# Doodlebot_v2_2025-06-04.net
KiCad netlist of a schematic drawn in EasyEDA Pro
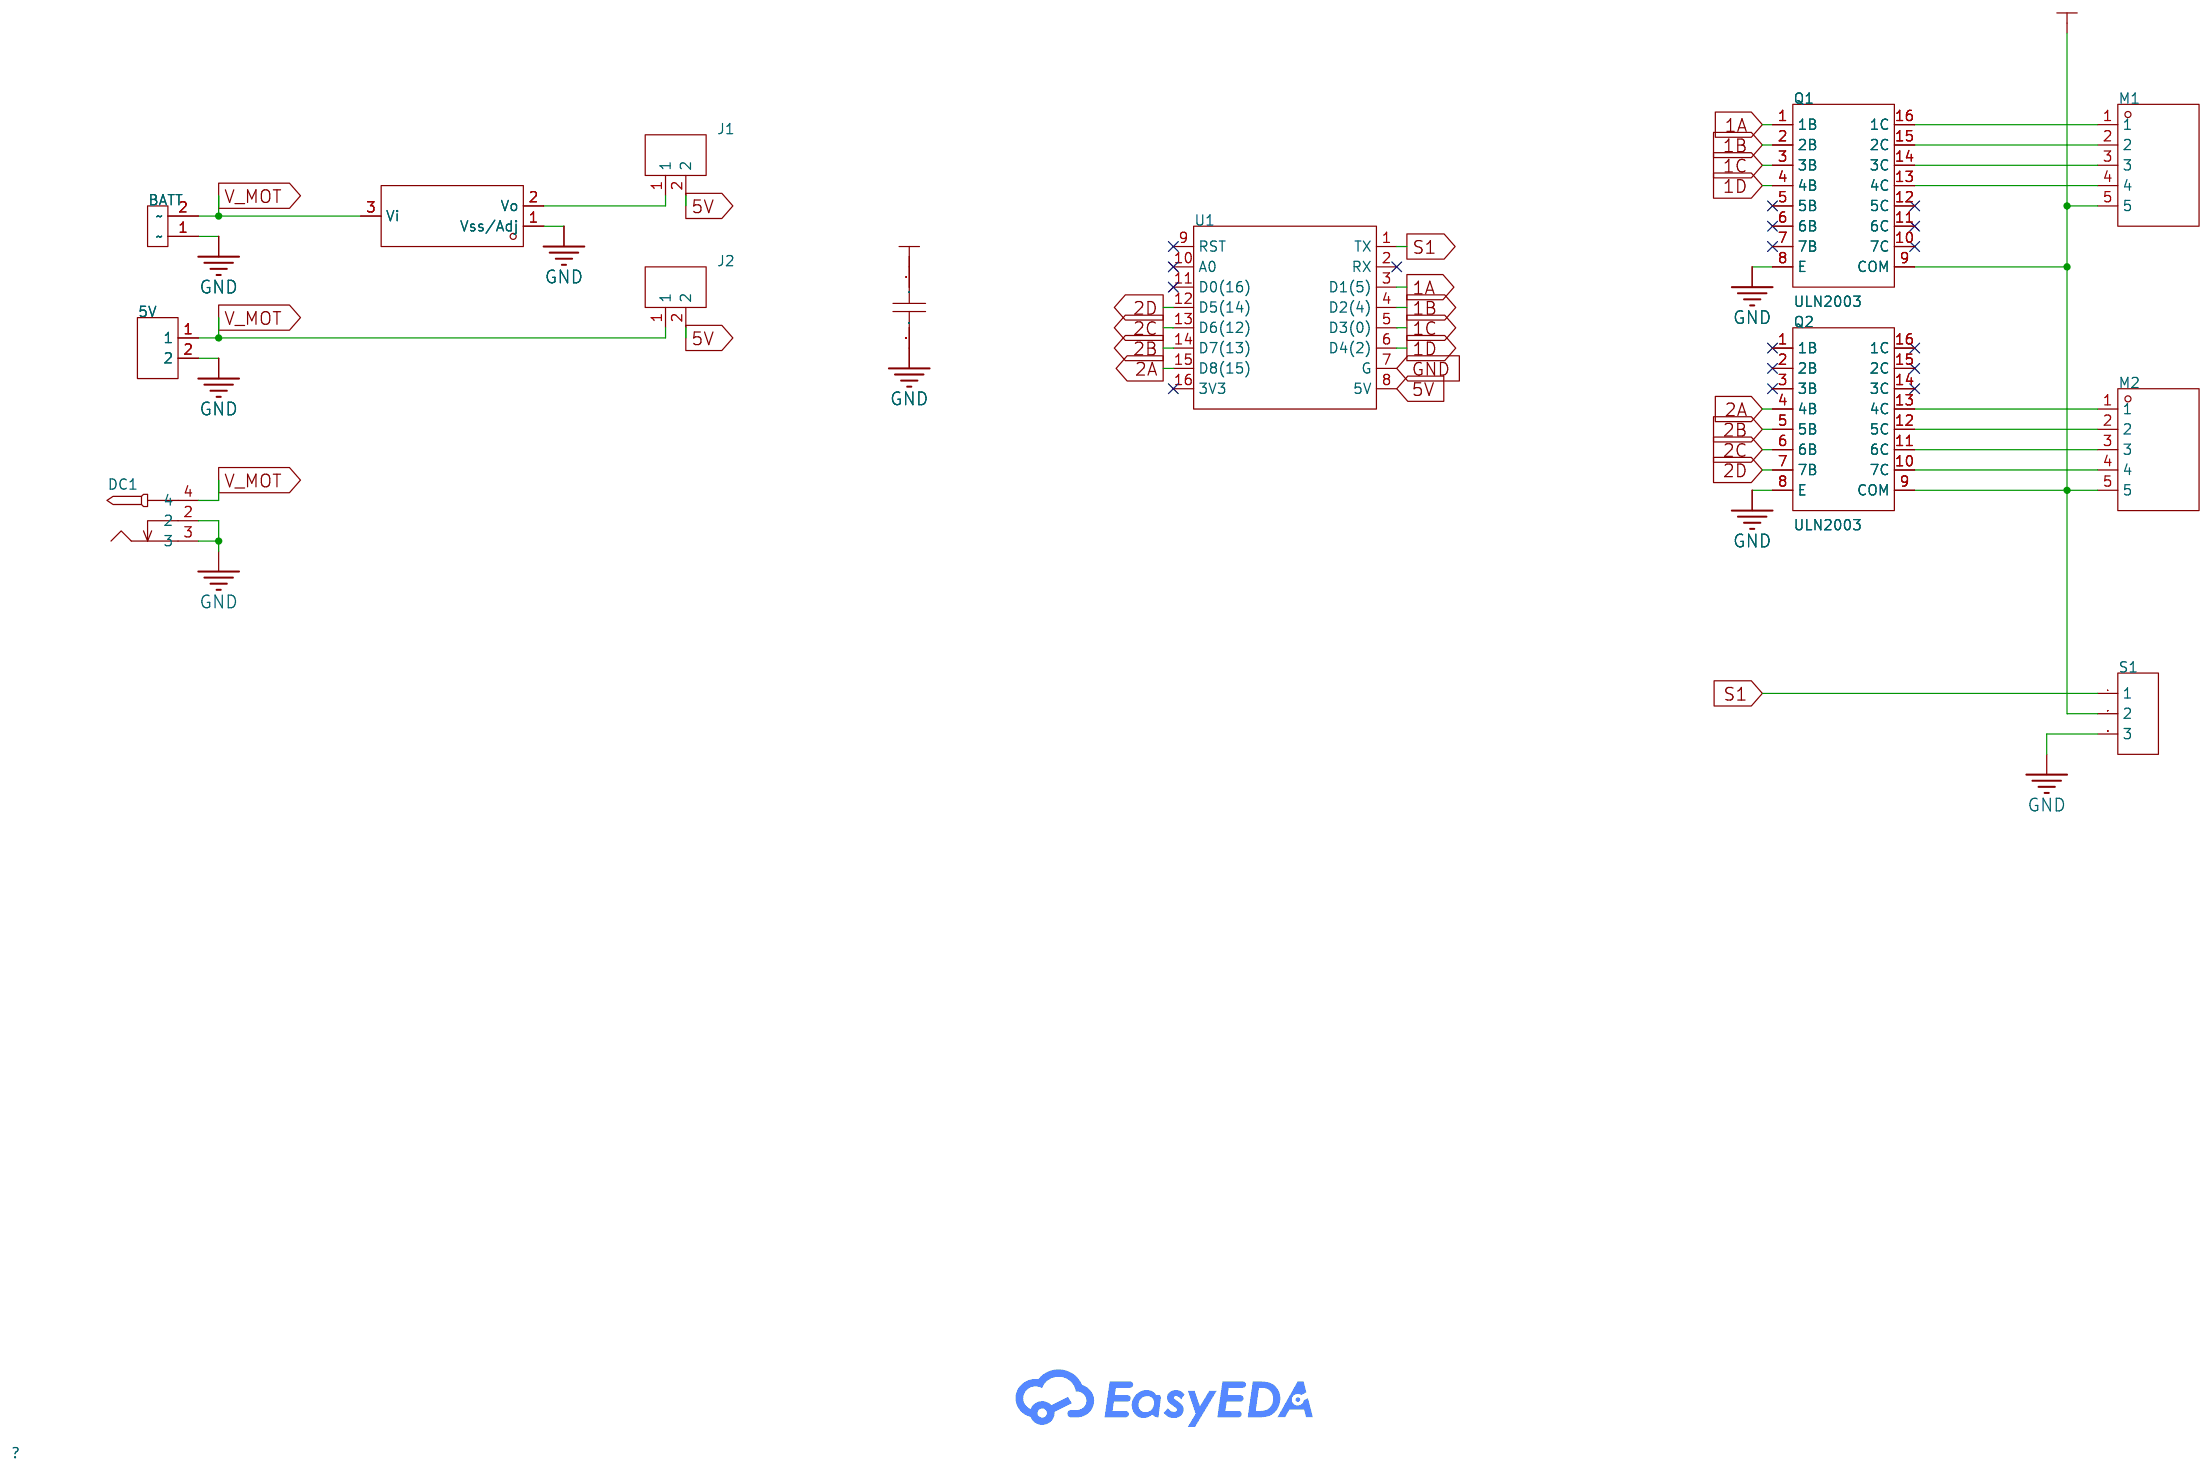
[diagram p0: schematic sheet]

(export (version "E")
  (design (tool "Eeschema 10.0.6"))
  (components
    (comp (ref "5V")
      (value "PZ254V-11-02P")
      (footprint "easyedapro:HDR-TH_2P-P2.54-V-M")
      (fields (field (name "Manufacturer") "XFCN(兴飞)"))
      (libsource (lib "easyedapro") (part "PZ254V-11-02P"))
    )
    (comp (ref "BATT")
      (value "JST-XH-B2B")
      (footprint "easyedapro:Connector_JST:JST_XH_B2B-XH-A_1x02_P2.50mm_Vertical")
      (fields (field (name "Manufacturer") "JST Sales America"))
      (libsource (lib "easyedapro") (part "StanleyProjects_J_JST-XH-B2B"))
    )
    (comp (ref "C1")
      (value "100nF")
      (footprint "easyedapro:C0603")
      (libsource (lib "easyedapro") (part "CAP"))
    )
    (comp (ref "DC1")
      (value "DC-005 2.0")
      (footprint "easyedapro:DC-IN-TH_DC-5520-1")
      (fields (field (name "Manufacturer") "BOOMELE(博穆精密)"))
      (libsource (lib "easyedapro") (part "DC-005 5.5-2.0MM"))
    )
    (comp (ref "J1")
      (value "PZ254V-11-02P")
      (footprint "easyedapro:HDR-TH_2P-P2.54-V-M")
      (fields (field (name "Manufacturer") "XFCN(兴飞)"))
      (libsource (lib "easyedapro") (part "PZ254V-11-02P"))
    )
    (comp (ref "J2")
      (value "PZ254V-11-02P")
      (footprint "easyedapro:HDR-TH_2P-P2.54-V-M")
      (fields (field (name "Manufacturer") "XFCN(兴飞)"))
      (libsource (lib "easyedapro") (part "PZ254V-11-02P"))
    )
    (comp (ref "M1")
      (value "B5B-XH-A(LF)(SN)")
      (footprint "easyedapro:CONN-TH_B5B-XH-A-LF-SN")
      (fields (field (name "Manufacturer") "JST"))
      (libsource (lib "easyedapro") (part "B5B-XH-A (LF)(SN)"))
    )
    (comp (ref "M2")
      (value "B5B-XH-A(LF)(SN)")
      (footprint "easyedapro:CONN-TH_B5B-XH-A-LF-SN")
      (fields (field (name "Manufacturer") "JST"))
      (libsource (lib "easyedapro") (part "B5B-XH-A (LF)(SN)"))
    )
    (comp (ref "Q1")
      (value "ULN2003")
      (footprint "easyedapro:DIP-16_L19.8-W6.5-P2.54-LS7.6-BL")
      (description "number of channels:Seven channels")
      (fields (field (name "Manufacturer") "YW(友旺)"))
      (libsource (lib "easyedapro") (part "ULN2003_C557872"))
    )
    (comp (ref "Q2")
      (value "ULN2003")
      (footprint "easyedapro:DIP-16_L19.8-W6.5-P2.54-LS7.6-BL")
      (description "number of channels:Seven channels")
      (fields (field (name "Manufacturer") "YW(友旺)"))
      (libsource (lib "easyedapro") (part "ULN2003_C557872"))
    )
    (comp (ref "S1")
      (value "2.54-1*3P针")
      (footprint "easyedapro:HDR-TH_3P-P2.54-V-M-1")
      (fields (field (name "Manufacturer") "BOOMELE(博穆精密)"))
      (libsource (lib "easyedapro") (part "Header-Male-2.54_1x3"))
    )
    (comp (ref "U1")
      (value "Wemos_D1_mini_Pro4")
      (footprint "easyedapro:DIP-16_WEMOS_D1_MINI_PRO4")
      (libsource (lib "easyedapro") (part "WEMOS_D1_MINI_PRO4"))
    )
    (comp (ref "U2")
      (value "AMS1117-5.0")
      (footprint "easyedapro:SOT-89-3_L4.5-W2.5-P1.50-LS4.0-BR-1")
      (fields (field (name "Manufacturer") "FOSAN(富捷/富信)"))
      (libsource (lib "easyedapro") (part "AMS1117-5.0_C42410722"))
    )
  )
  (nets
    (net (code "1") (name "1A") (class "Default")
      (node (ref "Q1") (pin "1") (pinfunction "1B_1") (pintype "unspecified"))
      (node (ref "U1") (pin "3") (pinfunction "D1(5)_3") (pintype "unspecified"))
    )
    (net (code "2") (name "1B") (class "Default")
      (node (ref "Q1") (pin "2") (pinfunction "2B_2") (pintype "unspecified"))
      (node (ref "U1") (pin "4") (pinfunction "D2(4)_4") (pintype "unspecified"))
    )
    (net (code "3") (name "1C") (class "Default")
      (node (ref "Q1") (pin "3") (pinfunction "3B_3") (pintype "unspecified"))
      (node (ref "U1") (pin "5") (pinfunction "D3(0)_5") (pintype "unspecified"))
    )
    (net (code "4") (name "1D") (class "Default")
      (node (ref "Q1") (pin "4") (pinfunction "4B_4") (pintype "unspecified"))
      (node (ref "U1") (pin "6") (pinfunction "D4(2)_6") (pintype "unspecified"))
    )
    (net (code "5") (name "2A") (class "Default")
      (node (ref "Q2") (pin "4") (pinfunction "4B_4") (pintype "unspecified"))
      (node (ref "U1") (pin "15") (pinfunction "D8(15)_15") (pintype "unspecified"))
    )
    (net (code "6") (name "2B") (class "Default")
      (node (ref "Q2") (pin "5") (pinfunction "5B_5") (pintype "unspecified"))
      (node (ref "U1") (pin "14") (pinfunction "D7(13)_14") (pintype "unspecified"))
    )
    (net (code "7") (name "2C") (class "Default")
      (node (ref "Q2") (pin "6") (pinfunction "6B_6") (pintype "unspecified"))
      (node (ref "U1") (pin "13") (pinfunction "D6(12)_13") (pintype "unspecified"))
    )
    (net (code "8") (name "2D") (class "Default")
      (node (ref "Q2") (pin "7") (pinfunction "7B_7") (pintype "unspecified"))
      (node (ref "U1") (pin "12") (pinfunction "D5(14)_12") (pintype "unspecified"))
    )
    (net (code "9") (name "5V") (class "Default")
      (node (ref "J1") (pin "2") (pinfunction "2_2") (pintype "unspecified"))
      (node (ref "J2") (pin "2") (pinfunction "2_2") (pintype "unspecified"))
      (node (ref "U1") (pin "8") (pinfunction "5V_8") (pintype "unspecified"))
    )
    (net (code "10") (name "GND") (class "Default")
      (node (ref "5V") (pin "2") (pinfunction "2_2") (pintype "unspecified"))
      (node (ref "BATT") (pin "1") (pinfunction "~_1") (pintype "unspecified"))
      (node (ref "C1") (pin "2") (pinfunction "2_2") (pintype "input"))
      (node (ref "DC1") (pin "2") (pinfunction "2_2") (pintype "unspecified"))
      (node (ref "DC1") (pin "3") (pinfunction "3_3") (pintype "unspecified"))
      (node (ref "Q1") (pin "8") (pinfunction "E_8") (pintype "unspecified"))
      (node (ref "Q2") (pin "8") (pinfunction "E_8") (pintype "unspecified"))
      (node (ref "S1") (pin "3") (pinfunction "3_3") (pintype "input"))
      (node (ref "U1") (pin "7") (pinfunction "G_7") (pintype "unspecified"))
      (node (ref "U2") (pin "1") (pinfunction "Vss/Adj_1") (pintype "unspecified"))
    )
    (net (code "11") (name "Net-(Q1-1C)") (class "Default")
      (node (ref "M1") (pin "1") (pinfunction "1_1") (pintype "unspecified"))
      (node (ref "Q1") (pin "16") (pinfunction "1C_16") (pintype "unspecified"))
    )
    (net (code "12") (name "Net-(Q1-2C)") (class "Default")
      (node (ref "M1") (pin "2") (pinfunction "2_2") (pintype "unspecified"))
      (node (ref "Q1") (pin "15") (pinfunction "2C_15") (pintype "unspecified"))
    )
    (net (code "13") (name "Net-(Q1-3C)") (class "Default")
      (node (ref "M1") (pin "3") (pinfunction "3_3") (pintype "unspecified"))
      (node (ref "Q1") (pin "14") (pinfunction "3C_14") (pintype "unspecified"))
    )
    (net (code "14") (name "Net-(Q1-4C)") (class "Default")
      (node (ref "M1") (pin "4") (pinfunction "4_4") (pintype "unspecified"))
      (node (ref "Q1") (pin "13") (pinfunction "4C_13") (pintype "unspecified"))
    )
    (net (code "15") (name "Net-(Q2-4C)") (class "Default")
      (node (ref "M2") (pin "1") (pinfunction "1_1") (pintype "unspecified"))
      (node (ref "Q2") (pin "13") (pinfunction "4C_13") (pintype "unspecified"))
    )
    (net (code "16") (name "Net-(Q2-5C)") (class "Default")
      (node (ref "M2") (pin "2") (pinfunction "2_2") (pintype "unspecified"))
      (node (ref "Q2") (pin "12") (pinfunction "5C_12") (pintype "unspecified"))
    )
    (net (code "17") (name "Net-(Q2-6C)") (class "Default")
      (node (ref "M2") (pin "3") (pinfunction "3_3") (pintype "unspecified"))
      (node (ref "Q2") (pin "11") (pinfunction "6C_11") (pintype "unspecified"))
    )
    (net (code "18") (name "Net-(Q2-7C)") (class "Default")
      (node (ref "M2") (pin "4") (pinfunction "4_4") (pintype "unspecified"))
      (node (ref "Q2") (pin "10") (pinfunction "7C_10") (pintype "unspecified"))
    )
    (net (code "19") (name "Net-(U2-Vo)") (class "Default")
      (node (ref "J1") (pin "1") (pinfunction "1_1") (pintype "unspecified"))
      (node (ref "U2") (pin "2") (pinfunction "Vo_2") (pintype "unspecified"))
    )
    (net (code "20") (name "S1") (class "Default")
      (node (ref "S1") (pin "1") (pinfunction "1_1") (pintype "input"))
      (node (ref "U1") (pin "1") (pinfunction "TX_1") (pintype "unspecified"))
    )
    (net (code "21") (name "V_MOT") (class "Default")
      (node (ref "5V") (pin "1") (pinfunction "1_1") (pintype "unspecified"))
      (node (ref "BATT") (pin "2") (pinfunction "~_2") (pintype "unspecified"))
      (node (ref "C1") (pin "1") (pinfunction "1_1") (pintype "input"))
      (node (ref "DC1") (pin "4") (pinfunction "4_4") (pintype "unspecified"))
      (node (ref "J2") (pin "1") (pinfunction "1_1") (pintype "unspecified"))
      (node (ref "M1") (pin "5") (pinfunction "5_5") (pintype "unspecified"))
      (node (ref "M2") (pin "5") (pinfunction "5_5") (pintype "unspecified"))
      (node (ref "Q1") (pin "9") (pinfunction "COM_9") (pintype "unspecified"))
      (node (ref "Q2") (pin "9") (pinfunction "COM_9") (pintype "unspecified"))
      (node (ref "S1") (pin "2") (pinfunction "2_2") (pintype "input"))
      (node (ref "U2") (pin "3") (pinfunction "Vi_3") (pintype "unspecified"))
    )
    (net (code "22") (name "unconnected-(Q1-5B-Pad5)") (class "Default")
      (node (ref "Q1") (pin "5") (pinfunction "5B_5") (pintype "unspecified+no_connect"))
    )
    (net (code "23") (name "unconnected-(Q1-5C-Pad12)") (class "Default")
      (node (ref "Q1") (pin "12") (pinfunction "5C_12") (pintype "unspecified+no_connect"))
    )
    (net (code "24") (name "unconnected-(Q1-6B-Pad6)") (class "Default")
      (node (ref "Q1") (pin "6") (pinfunction "6B_6") (pintype "unspecified+no_connect"))
    )
    (net (code "25") (name "unconnected-(Q1-6C-Pad11)") (class "Default")
      (node (ref "Q1") (pin "11") (pinfunction "6C_11") (pintype "unspecified+no_connect"))
    )
    (net (code "26") (name "unconnected-(Q1-7B-Pad7)") (class "Default")
      (node (ref "Q1") (pin "7") (pinfunction "7B_7") (pintype "unspecified+no_connect"))
    )
    (net (code "27") (name "unconnected-(Q1-7C-Pad10)") (class "Default")
      (node (ref "Q1") (pin "10") (pinfunction "7C_10") (pintype "unspecified+no_connect"))
    )
    (net (code "28") (name "unconnected-(Q2-1B-Pad1)") (class "Default")
      (node (ref "Q2") (pin "1") (pinfunction "1B_1") (pintype "unspecified+no_connect"))
    )
    (net (code "29") (name "unconnected-(Q2-1C-Pad16)") (class "Default")
      (node (ref "Q2") (pin "16") (pinfunction "1C_16") (pintype "unspecified+no_connect"))
    )
    (net (code "30") (name "unconnected-(Q2-2B-Pad2)") (class "Default")
      (node (ref "Q2") (pin "2") (pinfunction "2B_2") (pintype "unspecified+no_connect"))
    )
    (net (code "31") (name "unconnected-(Q2-2C-Pad15)") (class "Default")
      (node (ref "Q2") (pin "15") (pinfunction "2C_15") (pintype "unspecified+no_connect"))
    )
    (net (code "32") (name "unconnected-(Q2-3B-Pad3)") (class "Default")
      (node (ref "Q2") (pin "3") (pinfunction "3B_3") (pintype "unspecified+no_connect"))
    )
    (net (code "33") (name "unconnected-(Q2-3C-Pad14)") (class "Default")
      (node (ref "Q2") (pin "14") (pinfunction "3C_14") (pintype "unspecified+no_connect"))
    )
    (net (code "34") (name "unconnected-(U1-3V3-Pad16)") (class "Default")
      (node (ref "U1") (pin "16") (pinfunction "3V3_16") (pintype "unspecified+no_connect"))
    )
    (net (code "35") (name "unconnected-(U1-A0-Pad10)") (class "Default")
      (node (ref "U1") (pin "10") (pinfunction "A0_10") (pintype "unspecified+no_connect"))
    )
    (net (code "36") (name "unconnected-(U1-D0(16)-Pad11)") (class "Default")
      (node (ref "U1") (pin "11") (pinfunction "D0(16)_11") (pintype "unspecified+no_connect"))
    )
    (net (code "37") (name "unconnected-(U1-RST-Pad9)") (class "Default")
      (node (ref "U1") (pin "9") (pinfunction "RST_9") (pintype "unspecified+no_connect"))
    )
    (net (code "38") (name "unconnected-(U1-RX-Pad2)") (class "Default")
      (node (ref "U1") (pin "2") (pinfunction "RX_2") (pintype "unspecified+no_connect"))
    )
  )
)
